# Sheet_1_2024-04-11.net
KiCad netlist of a schematic drawn in Altium Designer
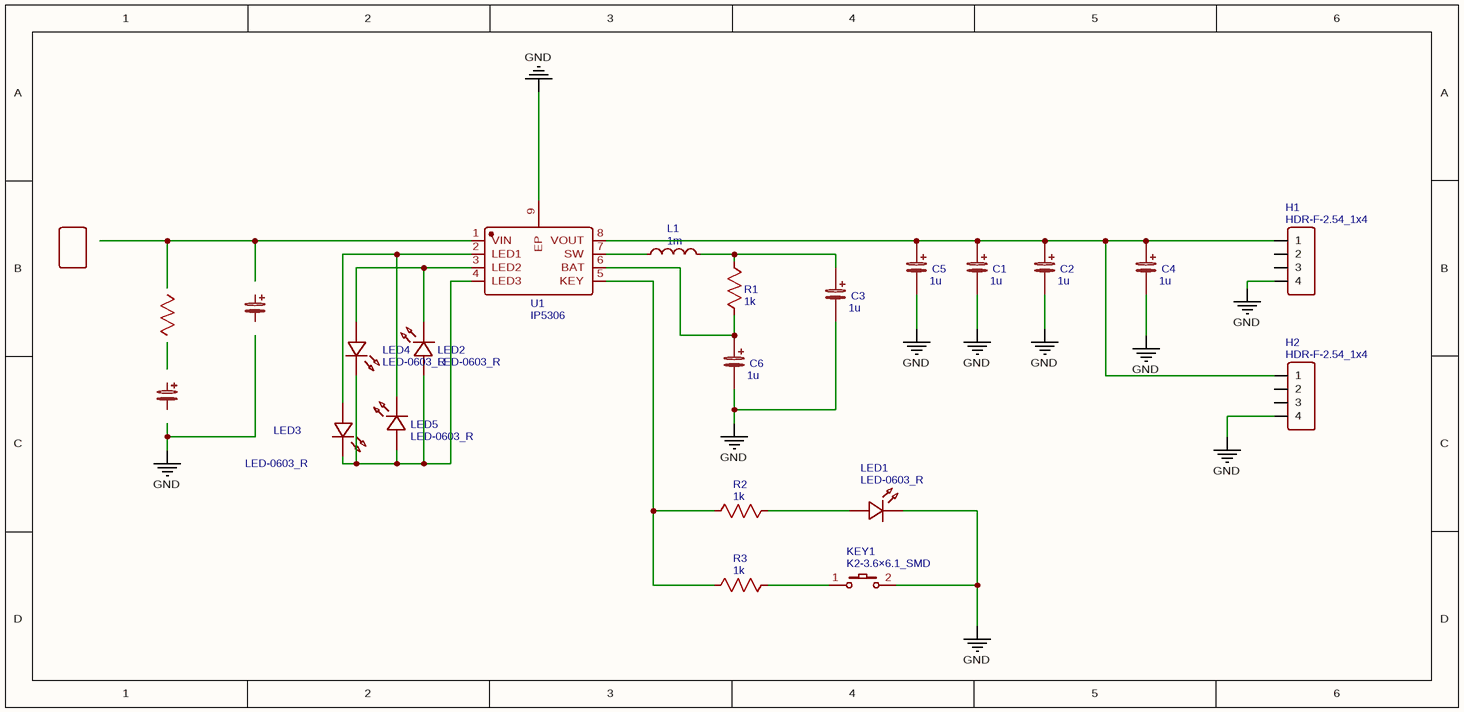
[diagram p0: Sheet_1_2024-04-11.schdoc]

(export (version "E")
  (design (tool "Eeschema 10.0.6"))
  (components
    (comp (ref "C1")
      (value "1u")
      (footprint "CASE-A_3216")
      (fields (field (name "CONTRIBUTOR") "LCEDA_Lib"))
      (libsource (lib "altium-import") (part "root_3_1u_"))
    )
    (comp (ref "C2")
      (value "1u")
      (footprint "CASE-A_3216")
      (fields (field (name "CONTRIBUTOR") "LCEDA_Lib"))
      (libsource (lib "altium-import") (part "root_3_1u_"))
    )
    (comp (ref "C3")
      (value "1u")
      (footprint "CASE-A_3216")
      (fields (field (name "CONTRIBUTOR") "LCEDA_Lib"))
      (libsource (lib "altium-import") (part "root_3_1u_"))
    )
    (comp (ref "C4")
      (value "1u")
      (footprint "CASE-A_3216")
      (fields (field (name "CONTRIBUTOR") "LCEDA_Lib"))
      (libsource (lib "altium-import") (part "root_3_1u_"))
    )
    (comp (ref "C5")
      (value "1u")
      (footprint "CASE-A_3216")
      (fields (field (name "CONTRIBUTOR") "LCEDA_Lib"))
      (libsource (lib "altium-import") (part "root_3_1u_"))
    )
    (comp (ref "C6")
      (value "1u")
      (footprint "CASE-A_3216")
      (fields (field (name "CONTRIBUTOR") "LCEDA_Lib"))
      (libsource (lib "altium-import") (part "root_3_1u_"))
    )
    (comp (ref "H1")
      (value "HDR-F-2.54_1x4")
      (footprint "HDR-F-2.54_1X4")
      (fields (field (name "CONTRIBUTOR") "LCEDA_Lib"))
      (libsource (lib "altium-import") (part "root_0_HDR-F-2.54_1x4_"))
    )
    (comp (ref "H2")
      (value "HDR-F-2.54_1x4")
      (footprint "HDR-F-2.54_1X4")
      (fields (field (name "CONTRIBUTOR") "LCEDA_Lib"))
      (libsource (lib "altium-import") (part "root_0_HDR-F-2.54_1x4_"))
    )
    (comp (ref "KEY1")
      (value "K2-3.6×6.1_SMD")
      (footprint "KEY-SMD_2P-L6.2-W3.6-LS8.0")
      (fields (field (name "MANUFACTURER PART") "K2-1107ST-A4SW-06") (field (name "CONTRIBUTOR") "LCEDA_Lib"))
      (libsource (lib "altium-import") (part "root_0_K2-3.6×6.1_SMD_"))
    )
    (comp (ref "L1")
      (value "1m")
      (footprint "L0603")
      (fields (field (name "CONTRIBUTOR") "LCEDA_Lib"))
      (libsource (lib "altium-import") (part "root_0_1m_"))
    )
    (comp (ref "LED1")
      (value "LED-0603_R")
      (footprint "LED0603_RED")
      (fields
        (field (name "MANUFACTURER") "EVERLIGHT(台湾亿光)")
        (field (name "MANUFACTURER PART") "19-217/R6C-AL1M2VY/3T")
        (field (name "CONTRIBUTOR") "LCEDA_01")
      )
      (libsource (lib "altium-import") (part "root_0_LED-0603_R_"))
    )
    (comp (ref "LED2")
      (value "LED-0603_R")
      (footprint "LED0603_RED")
      (fields
        (field (name "MANUFACTURER") "EVERLIGHT(台湾亿光)")
        (field (name "MANUFACTURER PART") "19-217/R6C-AL1M2VY/3T")
        (field (name "CONTRIBUTOR") "LCEDA_01")
      )
      (libsource (lib "altium-import") (part "root_1_LED-0603_R_"))
    )
    (comp (ref "LED3")
      (value "LED-0603_R")
      (footprint "LED0603_RED")
      (fields
        (field (name "MANUFACTURER") "EVERLIGHT(台湾亿光)")
        (field (name "MANUFACTURER PART") "19-217/R6C-AL1M2VY/3T")
        (field (name "CONTRIBUTOR") "LCEDA_01")
      )
      (libsource (lib "altium-import") (part "root_3_LED-0603_R_"))
    )
    (comp (ref "LED4")
      (value "LED-0603_R")
      (footprint "LED0603_RED")
      (fields
        (field (name "MANUFACTURER") "EVERLIGHT(台湾亿光)")
        (field (name "MANUFACTURER PART") "19-217/R6C-AL1M2VY/3T")
        (field (name "CONTRIBUTOR") "LCEDA_01")
      )
      (libsource (lib "altium-import") (part "root_3_LED-0603_R_"))
    )
    (comp (ref "LED5")
      (value "LED-0603_R")
      (footprint "LED0603_RED")
      (fields
        (field (name "MANUFACTURER") "EVERLIGHT(台湾亿光)")
        (field (name "MANUFACTURER PART") "19-217/R6C-AL1M2VY/3T")
        (field (name "CONTRIBUTOR") "LCEDA_01")
      )
      (libsource (lib "altium-import") (part "root_1_LED-0603_R_"))
    )
    (comp (ref "R1")
      (value "1k")
      (footprint "R0603")
      (fields (field (name "CONTRIBUTOR") "LCEDA_Lib"))
      (libsource (lib "altium-import") (part "root_3_1k_"))
    )
    (comp (ref "R2")
      (value "1k")
      (footprint "R0603")
      (fields (field (name "CONTRIBUTOR") "LCEDA_Lib"))
      (libsource (lib "altium-import") (part "root_0_1k_"))
    )
    (comp (ref "R3")
      (value "1k")
      (footprint "R0603")
      (fields (field (name "CONTRIBUTOR") "LCEDA_Lib"))
      (libsource (lib "altium-import") (part "root_0_1k_"))
    )
    (comp (ref "U1")
      (value "IP5306")
      (footprint "ESOP-8_L4.9-W3.9-P1.27-LS6.0-BL-EP")
      (fields (field (name "MANUFACTURER") "INJOINIC(英集芯)") (field (name "CONTRIBUTOR") "LCSC"))
      (libsource (lib "altium-import") (part "root_0_IP5306_"))
    )
  )
  (nets
    (net (code "1") (name "GND") (class "Default")
      (node (ref "C1") (pin "2") (pinfunction "2_2") (pintype "passive"))
      (node (ref "C2") (pin "2") (pinfunction "2_2") (pintype "passive"))
      (node (ref "C3") (pin "2") (pinfunction "2_2") (pintype "passive"))
      (node (ref "C4") (pin "2") (pinfunction "2_2") (pintype "passive"))
      (node (ref "C5") (pin "2") (pinfunction "2_2") (pintype "passive"))
      (node (ref "C6") (pin "2") (pinfunction "2_2") (pintype "passive"))
      (node (ref "H1") (pin "4") (pinfunction "4_4") (pintype "passive"))
      (node (ref "H2") (pin "4") (pinfunction "4_4") (pintype "passive"))
      (node (ref "KEY1") (pin "2") (pinfunction "2_2") (pintype "passive"))
      (node (ref "LED1") (pin "2") (pinfunction "2_2") (pintype "passive"))
      (node (ref "U1") (pin "9") (pinfunction "EP_9") (pintype "passive"))
    )
    (net (code "2") (name "Net-(C3-Pad1)") (class "Default")
      (node (ref "C3") (pin "1") (pinfunction "1_1") (pintype "passive"))
      (node (ref "L1") (pin "2") (pinfunction "2_2") (pintype "passive"))
      (node (ref "R1") (pin "1") (pinfunction "1_1") (pintype "passive"))
    )
    (net (code "3") (name "Net-(KEY1-Pad1)") (class "Default")
      (node (ref "KEY1") (pin "1") (pinfunction "1_1") (pintype "passive"))
      (node (ref "R3") (pin "2") (pinfunction "2_2") (pintype "passive"))
    )
    (net (code "4") (name "Net-(LED1-Pad1)") (class "Default")
      (node (ref "LED1") (pin "1") (pinfunction "1_1") (pintype "passive"))
      (node (ref "R2") (pin "2") (pinfunction "2_2") (pintype "passive"))
    )
    (net (code "5") (name "Net-(U1-BAT)") (class "Default")
      (node (ref "C6") (pin "1") (pinfunction "1_1") (pintype "passive"))
      (node (ref "R1") (pin "2") (pinfunction "2_2") (pintype "passive"))
      (node (ref "U1") (pin "6") (pinfunction "BAT_6") (pintype "passive"))
    )
    (net (code "6") (name "Net-(U1-KEY)") (class "Default")
      (node (ref "R2") (pin "1") (pinfunction "1_1") (pintype "passive"))
      (node (ref "R3") (pin "1") (pinfunction "1_1") (pintype "passive"))
      (node (ref "U1") (pin "5") (pinfunction "KEY_5") (pintype "passive"))
    )
    (net (code "7") (name "Net-(U1-LED1)") (class "Default")
      (node (ref "LED3") (pin "1") (pinfunction "1_1") (pintype "passive"))
      (node (ref "LED5") (pin "2") (pinfunction "2_2") (pintype "passive"))
      (node (ref "U1") (pin "2") (pinfunction "LED1_2") (pintype "passive"))
    )
    (net (code "8") (name "Net-(U1-LED2)") (class "Default")
      (node (ref "LED2") (pin "2") (pinfunction "2_2") (pintype "passive"))
      (node (ref "LED4") (pin "1") (pinfunction "1_1") (pintype "passive"))
      (node (ref "U1") (pin "3") (pinfunction "LED2_3") (pintype "passive"))
    )
    (net (code "9") (name "Net-(U1-LED3)") (class "Default")
      (node (ref "LED2") (pin "1") (pinfunction "1_1") (pintype "passive"))
      (node (ref "LED3") (pin "2") (pinfunction "2_2") (pintype "passive"))
      (node (ref "LED4") (pin "2") (pinfunction "2_2") (pintype "passive"))
      (node (ref "LED5") (pin "1") (pinfunction "1_1") (pintype "passive"))
      (node (ref "U1") (pin "4") (pinfunction "LED3_4") (pintype "passive"))
    )
    (net (code "10") (name "Net-(U1-SW)") (class "Default")
      (node (ref "L1") (pin "1") (pinfunction "1_1") (pintype "passive"))
      (node (ref "U1") (pin "7") (pinfunction "SW_7") (pintype "passive"))
    )
    (net (code "11") (name "Net-(U1-VOUT)") (class "Default")
      (node (ref "C1") (pin "1") (pinfunction "1_1") (pintype "passive"))
      (node (ref "C2") (pin "1") (pinfunction "1_1") (pintype "passive"))
      (node (ref "C4") (pin "1") (pinfunction "1_1") (pintype "passive"))
      (node (ref "C5") (pin "1") (pinfunction "1_1") (pintype "passive"))
      (node (ref "H1") (pin "1") (pinfunction "1_1") (pintype "passive"))
      (node (ref "H2") (pin "1") (pinfunction "1_1") (pintype "passive"))
      (node (ref "U1") (pin "8") (pinfunction "VOUT_8") (pintype "passive"))
    )
    (net (code "12") (name "unconnected-(H1-Pad2)") (class "Default")
      (node (ref "H1") (pin "2") (pinfunction "2_2") (pintype "passive"))
    )
    (net (code "13") (name "unconnected-(H1-Pad3)") (class "Default")
      (node (ref "H1") (pin "3") (pinfunction "3_3") (pintype "passive"))
    )
    (net (code "14") (name "unconnected-(H2-Pad2)") (class "Default")
      (node (ref "H2") (pin "2") (pinfunction "2_2") (pintype "passive"))
    )
    (net (code "15") (name "unconnected-(H2-Pad3)") (class "Default")
      (node (ref "H2") (pin "3") (pinfunction "3_3") (pintype "passive"))
    )
    (net (code "16") (name "unconnected-(U1-VIN-Pad1)") (class "Default")
      (node (ref "U1") (pin "1") (pinfunction "VIN_1") (pintype "passive"))
    )
  )
)
